# GSM.net
KiCad netlist of a schematic drawn in Altium Designer
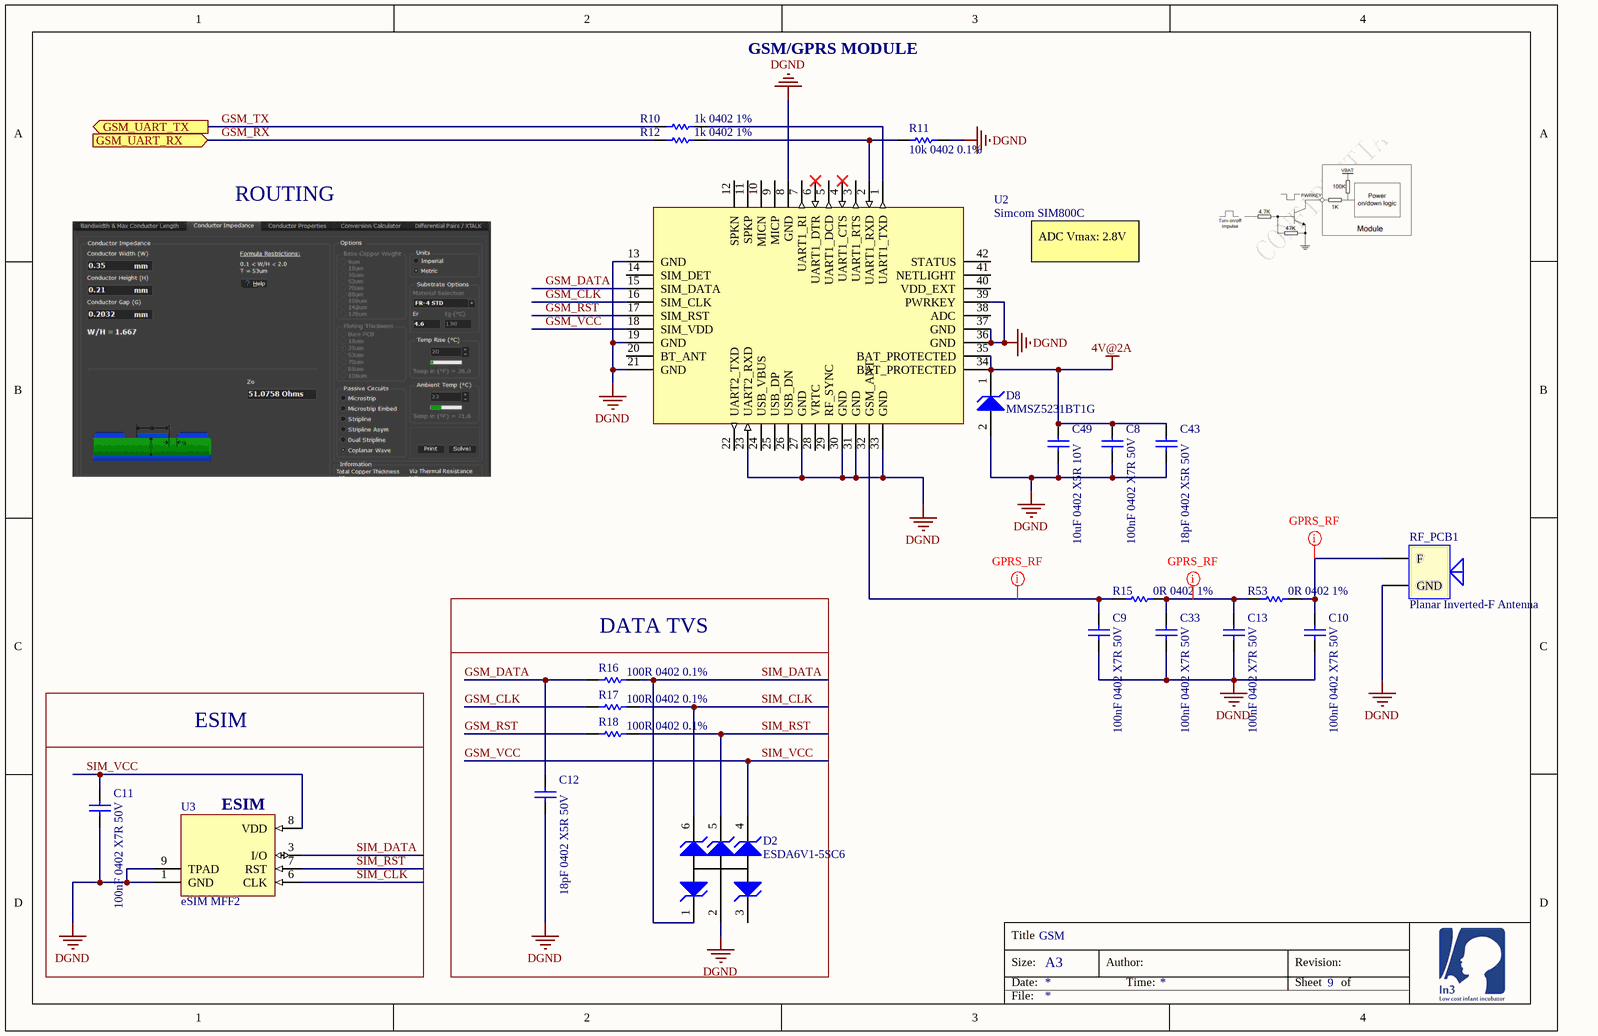
[diagram p0: GSM.SchDoc]

(export (version "E")
  (design (tool "Eeschema 10.0.6"))
  (components
    (comp (ref "C8")
      (value "100nF 0402 X7R 50V")
      (footprint "CAPC1005X55X25NL5T10")
      (libsource (lib "Altium Content Vault") (part "CAP-NP-2"))
    )
    (comp (ref "C9")
      (value "100nF 0402 X7R 50V")
      (footprint "CAPC1005X55X25NL5T10")
      (libsource (lib "Altium Content Vault") (part "CAP-NP-2"))
    )
    (comp (ref "C10")
      (value "100nF 0402 X7R 50V")
      (footprint "CAPC1005X55X25NL5T10")
      (libsource (lib "Altium Content Vault") (part "CAP-NP-2"))
    )
    (comp (ref "C11")
      (value "100nF 0402 X7R 50V")
      (footprint "CAPC1005X55X25NL5T10")
      (libsource (lib "Altium Content Vault") (part "CAP-NP-2"))
    )
    (comp (ref "C12")
      (value "18pF 0402 X5R 50V")
      (footprint "CAPC1005X55X25NL5T10")
      (libsource (lib "Altium Content Vault") (part "CAP-NP-2"))
    )
    (comp (ref "C13")
      (value "100nF 0402 X7R 50V")
      (footprint "CAPC1005X55X25NL5T10")
      (libsource (lib "Altium Content Vault") (part "CAP-NP-2"))
    )
    (comp (ref "C33")
      (value "100nF 0402 X7R 50V")
      (footprint "CAPC1005X55X25NL5T10")
      (libsource (lib "Altium Content Vault") (part "CAP-NP-2"))
    )
    (comp (ref "C43")
      (value "18pF 0402 X5R 50V")
      (footprint "CAPC1005X55X25NL5T10")
      (libsource (lib "Altium Content Vault") (part "CAP-NP-2"))
    )
    (comp (ref "C49")
      (value "10uF 0402 X5R 10V")
      (footprint "CAPC1005X55X25NL5T10")
      (libsource (lib "Altium Content Vault") (part "CAP-NP-2"))
    )
    (comp (ref "D2")
      (value "ESDA6V1-5SC6")
      (footprint "MF06A_N")
      (description "ESDA Series 5 Channel 6.1 V 50 pF SMT Uni Directional Transil Array - SOT-23-6L")
      (libsource (lib "in3ator_components") (part "CMP-924f5b40f9684d88-1"))
    )
    (comp (ref "D8")
      (value "MMSZ5231BT1G")
      (footprint "ONSC-SOD-123-2-425-04_V")
      (description "Zener Voltage Regulator, 500 mW, 2-Pin SOD-123, Pb-Free, Tape and Reel")
      (fields (field (name "MANUFACTURER") "On Semiconductor"))
      (libsource (lib "Altium Content Vault") (part "ONSC-K1A2-2"))
    )
    (comp (ref "R10")
      (value "1k 0402 1%")
      (footprint "RESC1005X40X25ML05T10")
      (libsource (lib "Altium Content Vault") (part "RES"))
    )
    (comp (ref "R11")
      (value "10k 0402 0.1%")
      (footprint "RESC1005X40X25ML05T10")
      (libsource (lib "Altium Content Vault") (part "RES"))
    )
    (comp (ref "R12")
      (value "1k 0402 1%")
      (footprint "RESC1005X40X25ML05T10")
      (libsource (lib "Altium Content Vault") (part "RES"))
    )
    (comp (ref "R15")
      (value "0R 0402 1%")
      (footprint "RESC1005X40X25ML05T10")
      (libsource (lib "Altium Content Vault") (part "RES"))
    )
    (comp (ref "R16")
      (value "100R 0402 0.1%")
      (footprint "RESC1005X40X25ML05T10")
      (libsource (lib "Altium Content Vault") (part "RES"))
    )
    (comp (ref "R17")
      (value "100R 0402 0.1%")
      (footprint "RESC1005X40X25ML05T10")
      (libsource (lib "Altium Content Vault") (part "RES"))
    )
    (comp (ref "R18")
      (value "100R 0402 0.1%")
      (footprint "RESC1005X40X25ML05T10")
      (libsource (lib "Altium Content Vault") (part "RES"))
    )
    (comp (ref "R53")
      (value "0R 0402 1%")
      (footprint "RESC1005X40X25ML05T10")
      (libsource (lib "Altium Content Vault") (part "RES"))
    )
    (comp (ref "RF_PCB1")
      (value "Planar Inverted-F Antenna")
      (footprint "PCB-k9titb4465gfk1ijwrnj-1")
      (description "GSM900 and GSM1800  Frequency Bands PCB antenna")
      (libsource (lib "in3ator") (part "CMP-e704afk8c25r4a5ypw1c-12"))
    )
    (comp (ref "U2")
      (value "Simcom SIM800C")
      (footprint "SIM800C")
      (description "Module: GSM/Bluetooth; GPRS; 2G; 1800MHz, 900MHz; 85.6kbps; SMD")
      (fields (field (name "MANUFACTURER PART NUMBER") "SIM800C") (field (name "LCSC PART") "C69120"))
      (libsource (lib "in3ator") (part "CMP-72dbb8ea0133ad1c-5"))
    )
    (comp (ref "U3")
      (value "eSIM MFF2")
      (footprint "SON127P600X95_HS-9N")
      (description "Embedded SIM card in MFF2")
      (libsource (lib "in3ator") (part "CMP-ce8f06c57f401148-2"))
    )
  )
  (nets
    (net (code "1") (name "/GSM_CLK") (class "Default")
      (node (ref "R17") (pin "2") (pinfunction "2_2") (pintype "passive"))
      (node (ref "U2") (pin "16") (pinfunction "SIM_CLK_16") (pintype "passive"))
    )
    (net (code "2") (name "/GSM_DATA") (class "Default")
      (node (ref "C12") (pin "2") (pinfunction "2_2") (pintype "passive"))
      (node (ref "R16") (pin "2") (pinfunction "2_2") (pintype "passive"))
      (node (ref "U2") (pin "15") (pinfunction "SIM_DATA_15") (pintype "passive"))
    )
    (net (code "3") (name "/GSM_RST") (class "Default")
      (node (ref "R18") (pin "2") (pinfunction "2_2") (pintype "passive"))
      (node (ref "U2") (pin "17") (pinfunction "SIM_RST_17") (pintype "passive"))
    )
    (net (code "4") (name "/GSM_RX") (class "Default")
      (node (ref "R12") (pin "2") (pinfunction "2_2") (pintype "passive"))
    )
    (net (code "5") (name "/GSM_TX") (class "Default")
      (node (ref "R10") (pin "2") (pinfunction "2_2") (pintype "passive"))
    )
    (net (code "6") (name "/GSM_VCC") (class "Default")
      (node (ref "C11") (pin "2") (pinfunction "2_2") (pintype "passive"))
      (node (ref "D2") (pin "4") (pinfunction "A_4") (pintype "passive"))
      (node (ref "U2") (pin "18") (pinfunction "SIM_VDD_18") (pintype "passive"))
      (node (ref "U3") (pin "8") (pinfunction "VDD_8") (pintype "input"))
    )
    (net (code "7") (name "/SIM_CLK") (class "Default")
      (node (ref "D2") (pin "6") (pinfunction "A_6") (pintype "passive"))
      (node (ref "R17") (pin "1") (pinfunction "1_1") (pintype "passive"))
      (node (ref "U3") (pin "6") (pinfunction "CLK_6") (pintype "input"))
    )
    (net (code "8") (name "/SIM_DATA") (class "Default")
      (node (ref "D2") (pin "1") (pinfunction "K_1") (pintype "passive"))
      (node (ref "R16") (pin "1") (pinfunction "1_1") (pintype "passive"))
      (node (ref "U3") (pin "3") (pinfunction "I/O_3") (pintype "bidirectional"))
    )
    (net (code "9") (name "/SIM_RST") (class "Default")
      (node (ref "D2") (pin "5") (pinfunction "A_5") (pintype "passive"))
      (node (ref "R18") (pin "1") (pinfunction "1_1") (pintype "passive"))
      (node (ref "U3") (pin "7") (pinfunction "RST_7") (pintype "input"))
    )
    (net (code "10") (name "4V@2A") (class "Default")
      (node (ref "C43") (pin "2") (pinfunction "2_2") (pintype "passive"))
      (node (ref "C49") (pin "2") (pinfunction "2_2") (pintype "passive"))
      (node (ref "C8") (pin "2") (pinfunction "2_2") (pintype "passive"))
      (node (ref "D8") (pin "1") (pinfunction "K_1") (pintype "passive"))
      (node (ref "U2") (pin "34") (pinfunction "BAT_PROTECTED_34") (pintype "passive"))
      (node (ref "U2") (pin "35") (pinfunction "BAT_PROTECTED_35") (pintype "passive"))
    )
    (net (code "11") (name "DGND") (class "Default")
      (node (ref "C10") (pin "1") (pinfunction "1_1") (pintype "passive"))
      (node (ref "C11") (pin "1") (pinfunction "1_1") (pintype "passive"))
      (node (ref "C12") (pin "1") (pinfunction "1_1") (pintype "passive"))
      (node (ref "C13") (pin "1") (pinfunction "1_1") (pintype "passive"))
      (node (ref "C33") (pin "1") (pinfunction "1_1") (pintype "passive"))
      (node (ref "C43") (pin "1") (pinfunction "1_1") (pintype "passive"))
      (node (ref "C49") (pin "1") (pinfunction "1_1") (pintype "passive"))
      (node (ref "C8") (pin "1") (pinfunction "1_1") (pintype "passive"))
      (node (ref "C9") (pin "1") (pinfunction "1_1") (pintype "passive"))
      (node (ref "D2") (pin "2") (pinfunction "K_2") (pintype "passive"))
      (node (ref "D8") (pin "2") (pinfunction "A_2") (pintype "passive"))
      (node (ref "R11") (pin "1") (pinfunction "1_1") (pintype "passive"))
      (node (ref "RF_PCB1") (pin "2") (pinfunction "GND_2") (pintype "passive"))
      (node (ref "U2") (pin "13") (pinfunction "GND_13") (pintype "passive"))
      (node (ref "U2") (pin "19") (pinfunction "GND_19") (pintype "passive"))
      (node (ref "U2") (pin "21") (pinfunction "GND_21") (pintype "passive"))
      (node (ref "U2") (pin "23") (pinfunction "UART2_RXD_23") (pintype "input"))
      (node (ref "U2") (pin "27") (pinfunction "GND_27") (pintype "power_in"))
      (node (ref "U2") (pin "30") (pinfunction "GND_30") (pintype "power_in"))
      (node (ref "U2") (pin "31") (pinfunction "GND_31") (pintype "power_in"))
      (node (ref "U2") (pin "33") (pinfunction "GND_33") (pintype "power_in"))
      (node (ref "U2") (pin "36") (pinfunction "GND_36") (pintype "power_in"))
      (node (ref "U2") (pin "37") (pinfunction "GND_37") (pintype "power_in"))
      (node (ref "U2") (pin "39") (pinfunction "PWRKEY_39") (pintype "passive"))
      (node (ref "U2") (pin "8") (pinfunction "GND_8") (pintype "power_in"))
      (node (ref "U3") (pin "1") (pinfunction "GND_1") (pintype "power_in"))
      (node (ref "U3") (pin "9") (pinfunction "TPAD_9") (pintype "power_in"))
    )
    (net (code "12") (name "Net-(C13-Pad2)") (class "Default")
      (node (ref "C13") (pin "2") (pinfunction "2_2") (pintype "passive"))
      (node (ref "C33") (pin "2") (pinfunction "2_2") (pintype "passive"))
      (node (ref "R15") (pin "1") (pinfunction "1_1") (pintype "passive"))
      (node (ref "R53") (pin "2") (pinfunction "2_2") (pintype "passive"))
    )
    (net (code "13") (name "Net-(RF_PCB1-F)") (class "Default")
      (node (ref "C10") (pin "2") (pinfunction "2_2") (pintype "passive"))
      (node (ref "R53") (pin "1") (pinfunction "1_1") (pintype "passive"))
      (node (ref "RF_PCB1") (pin "1") (pinfunction "F_1") (pintype "passive"))
    )
    (net (code "14") (name "Net-(U2-GSM_ANT)") (class "Default")
      (node (ref "C9") (pin "2") (pinfunction "2_2") (pintype "passive"))
      (node (ref "R15") (pin "2") (pinfunction "2_2") (pintype "passive"))
      (node (ref "U2") (pin "32") (pinfunction "GSM_ANT_32") (pintype "passive"))
    )
    (net (code "15") (name "Net-(U2-UART1_RXD)") (class "Default")
      (node (ref "R11") (pin "2") (pinfunction "2_2") (pintype "passive"))
      (node (ref "R12") (pin "1") (pinfunction "1_1") (pintype "passive"))
      (node (ref "U2") (pin "2") (pinfunction "UART1_RXD_2") (pintype "input"))
    )
    (net (code "16") (name "Net-(U2-UART1_TXD)") (class "Default")
      (node (ref "R10") (pin "1") (pinfunction "1_1") (pintype "passive"))
      (node (ref "U2") (pin "1") (pinfunction "UART1_TXD_1") (pintype "output"))
    )
    (net (code "17") (name "unconnected-(D2-K-Pad3)") (class "Default")
      (node (ref "D2") (pin "3") (pinfunction "K_3") (pintype "passive"))
    )
    (net (code "18") (name "unconnected-(U2-ADC-Pad38)") (class "Default")
      (node (ref "U2") (pin "38") (pinfunction "ADC_38") (pintype "passive"))
    )
    (net (code "19") (name "unconnected-(U2-BT_ANT-Pad20)") (class "Default")
      (node (ref "U2") (pin "20") (pinfunction "BT_ANT_20") (pintype "passive"))
    )
    (net (code "20") (name "unconnected-(U2-MICN-Pad10)") (class "Default")
      (node (ref "U2") (pin "10") (pinfunction "MICN_10") (pintype "passive"))
    )
    (net (code "21") (name "unconnected-(U2-MICP-Pad9)") (class "Default")
      (node (ref "U2") (pin "9") (pinfunction "MICP_9") (pintype "passive"))
    )
    (net (code "22") (name "unconnected-(U2-NETLIGHT-Pad41)") (class "Default")
      (node (ref "U2") (pin "41") (pinfunction "NETLIGHT_41") (pintype "passive"))
    )
    (net (code "23") (name "unconnected-(U2-RF_SYNC-Pad29)") (class "Default")
      (node (ref "U2") (pin "29") (pinfunction "RF_SYNC_29") (pintype "passive"))
    )
    (net (code "24") (name "unconnected-(U2-SIM_DET-Pad14)") (class "Default")
      (node (ref "U2") (pin "14") (pinfunction "SIM_DET_14") (pintype "passive"))
    )
    (net (code "25") (name "unconnected-(U2-SPKN-Pad12)") (class "Default")
      (node (ref "U2") (pin "12") (pinfunction "SPKN_12") (pintype "passive"))
    )
    (net (code "26") (name "unconnected-(U2-SPKP-Pad11)") (class "Default")
      (node (ref "U2") (pin "11") (pinfunction "SPKP_11") (pintype "passive"))
    )
    (net (code "27") (name "unconnected-(U2-STATUS-Pad42)") (class "Default")
      (node (ref "U2") (pin "42") (pinfunction "STATUS_42") (pintype "passive"))
    )
    (net (code "28") (name "unconnected-(U2-UART1_CTS-Pad4)") (class "Default")
      (node (ref "U2") (pin "4") (pinfunction "UART1_CTS_4") (pintype "input+no_connect"))
    )
    (net (code "29") (name "unconnected-(U2-UART1_DCD-Pad5)") (class "Default")
      (node (ref "U2") (pin "5") (pinfunction "UART1_DCD_5") (pintype "output"))
    )
    (net (code "30") (name "unconnected-(U2-UART1_DTR-Pad6)") (class "Default")
      (node (ref "U2") (pin "6") (pinfunction "UART1_DTR_6") (pintype "input+no_connect"))
    )
    (net (code "31") (name "unconnected-(U2-UART1_RI-Pad7)") (class "Default")
      (node (ref "U2") (pin "7") (pinfunction "UART1_RI_7") (pintype "output"))
    )
    (net (code "32") (name "unconnected-(U2-UART1_RTS-Pad3)") (class "Default")
      (node (ref "U2") (pin "3") (pinfunction "UART1_RTS_3") (pintype "output"))
    )
    (net (code "33") (name "unconnected-(U2-UART2_TXD-Pad22)") (class "Default")
      (node (ref "U2") (pin "22") (pinfunction "UART2_TXD_22") (pintype "output"))
    )
    (net (code "34") (name "unconnected-(U2-USB_DN-Pad26)") (class "Default")
      (node (ref "U2") (pin "26") (pinfunction "USB_DN_26") (pintype "passive"))
    )
    (net (code "35") (name "unconnected-(U2-USB_DP-Pad25)") (class "Default")
      (node (ref "U2") (pin "25") (pinfunction "USB_DP_25") (pintype "passive"))
    )
    (net (code "36") (name "unconnected-(U2-USB_VBUS-Pad24)") (class "Default")
      (node (ref "U2") (pin "24") (pinfunction "USB_VBUS_24") (pintype "passive"))
    )
    (net (code "37") (name "unconnected-(U2-VDD_EXT-Pad40)") (class "Default")
      (node (ref "U2") (pin "40") (pinfunction "VDD_EXT_40") (pintype "passive"))
    )
    (net (code "38") (name "unconnected-(U2-VRTC-Pad28)") (class "Default")
      (node (ref "U2") (pin "28") (pinfunction "VRTC_28") (pintype "passive"))
    )
  )
)
